# Connectors.net
KiCad netlist of a schematic drawn in Altium Designer
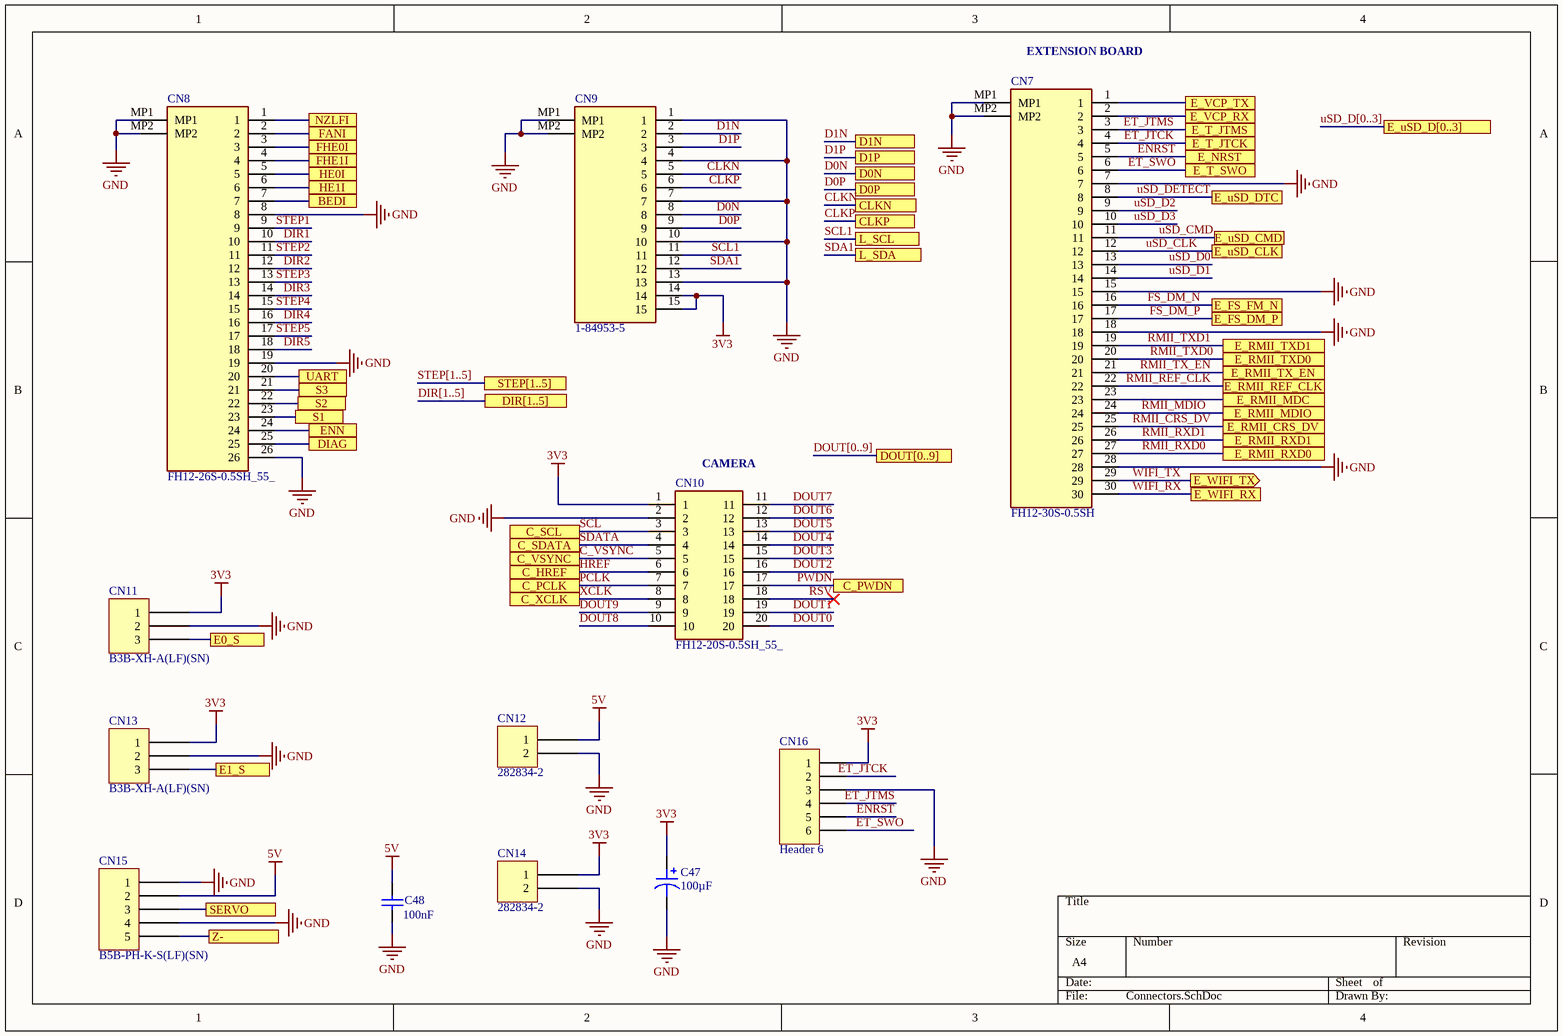
[diagram p0: Connectors.SchDoc]

(export (version "E")
  (design (tool "Eeschema 10.0.6"))
  (components
    (comp (ref "C47")
      (value "100µF")
      (footprint "CAP ALSMD POLY 5.3MM H6.0MM")
      (description "CAP ALUM POLY 100UF 20% 6.3V SMD")
      (fields
        (field (name "PART NUMBER") "6SVPC100M")
        (field (name "MANUFACTURER") "Panasonic Electronic Components")
      )
      (libsource (lib "Celestial Altium Library - altium_library") (part "Polarised Capacitor"))
    )
    (comp (ref "C48")
      (value "100nF")
      (footprint "1608[0603]")
      (description "Capacitor")
      (fields (field (name "Comment") "X5R") (field (name "PUBLISHER") "Altium Limited"))
      (libsource (lib "Miscellaneous Devices") (part "Cap"))
    )
    (comp (ref "CN7")
      (value "FH12-30S-0.5SH")
      (footprint "SamacSys:FH1230S05SH")
      (description "Connector")
      (libsource (lib "*") (part "FH12-30S-0.5SH"))
    )
    (comp (ref "CN8")
      (value "FH12-26S-0.5SH_55_")
      (footprint "SamacSys:FH1226S05SH55")
      (description "Connector")
      (fields
        (field (name "MANUFACTURER_PART_NUMBER") "FH12-26S-0.5SH(55)")
        (field (name "MOUSER PART NUMBER") "798-FH12-26S-0.5SH55")
      )
      (libsource (lib "SamacSys") (part "FH12-26S-0.5SH_55_"))
    )
    (comp (ref "CN9")
      (value "1-84953-5")
      (footprint "SamacSys:1849535")
      (description "Connector")
      (fields (field (name "MOUSER PART NUMBER") "571-1-84953-5"))
      (libsource (lib "*") (part "1-84953-5"))
    )
    (comp (ref "CN10")
      (value "FH12-20S-0.5SH_55_")
      (footprint "SamacSys:FH12-20S-0.5SH(55)")
      (description "Connector")
      (fields
        (field (name "MANUFACTURER_PART_NUMBER") "FH12-20S-0.5SH(55)")
        (field (name "MOUSER PART NUMBER") "798-FH12-20S-0.5SH55")
      )
      (libsource (lib "*") (part "FH12-20S-0.5SH_55_"))
    )
    (comp (ref "CN11")
      (value "B3B-XH-A(LF)(SN)")
      (footprint "JST XH B3B-XH-A")
      (description "CONN HEADER VERT 3POS 2.5MM")
      (fields (field (name "MANUFACTURER") "JST Sales America Inc."))
      (libsource (lib "Celestial Altium Library - altium_library") (part "3 Pin"))
    )
    (comp (ref "CN12")
      (value "282834-2")
      (footprint "TE 282834-2")
      (description "TERM BLK 2P SIDE ENT 2.54MM PCB")
      (fields (field (name "MANUFACTURER") "TE Connectivity AMP Connectors") (field (name "VOLTAGE") "150V"))
      (libsource (lib "Celestial Altium Library - altium_library") (part "2 Pin"))
    )
    (comp (ref "CN13")
      (value "B3B-XH-A(LF)(SN)")
      (footprint "JST XH B3B-XH-A")
      (description "CONN HEADER VERT 3POS 2.5MM")
      (fields (field (name "MANUFACTURER") "JST Sales America Inc."))
      (libsource (lib "Celestial Altium Library - altium_library") (part "3 Pin"))
    )
    (comp (ref "CN14")
      (value "282834-2")
      (footprint "TE 282834-2")
      (description "TERM BLK 2P SIDE ENT 2.54MM PCB")
      (fields (field (name "MANUFACTURER") "TE Connectivity AMP Connectors") (field (name "VOLTAGE") "150V"))
      (libsource (lib "Celestial Altium Library - altium_library") (part "2 Pin"))
    )
    (comp (ref "CN15")
      (value "B5B-PH-K-S(LF)(SN)")
      (footprint "JST B5B-PH-K")
      (description "CONN HEADER VERT 5POS 2MM")
      (fields (field (name "MANUFACTURER") "JST Sales America Inc."))
      (libsource (lib "Celestial Altium Library - altium_library") (part "5 Pin"))
    )
    (comp (ref "CN16")
      (value "Header 6")
      (footprint "HDR1X6")
      (description "Header, 6-Pin")
      (fields (field (name "PUBLISHER") "Altium Limited"))
      (libsource (lib "Miscellaneous Connectors") (part "Header 6"))
    )
  )
  (nets
    (net (code "1") (name "/BEDI") (class "Default")
      (node (ref "CN8") (pin "7") (pinfunction "7_7") (pintype "passive"))
    )
    (net (code "2") (name "/CLKN") (class "Default")
      (node (ref "CN9") (pin "5") (pinfunction "5_5") (pintype "passive"))
    )
    (net (code "3") (name "/CLKP") (class "Default")
      (node (ref "CN9") (pin "6") (pinfunction "6_6") (pintype "passive"))
    )
    (net (code "4") (name "/C_VSYNC") (class "Default")
      (node (ref "CN10") (pin "5") (pinfunction "5_5") (pintype "passive"))
    )
    (net (code "5") (name "/D0N") (class "Default")
      (node (ref "CN9") (pin "8") (pinfunction "8_8") (pintype "passive"))
    )
    (net (code "6") (name "/D0P") (class "Default")
      (node (ref "CN9") (pin "9") (pinfunction "9_9") (pintype "passive"))
    )
    (net (code "7") (name "/D1N") (class "Default")
      (node (ref "CN9") (pin "2") (pinfunction "2_2") (pintype "passive"))
    )
    (net (code "8") (name "/D1P") (class "Default")
      (node (ref "CN9") (pin "3") (pinfunction "3_3") (pintype "passive"))
    )
    (net (code "9") (name "/DIAG") (class "Default")
      (node (ref "CN8") (pin "25") (pinfunction "25_25") (pintype "passive"))
    )
    (net (code "10") (name "/DIR1") (class "Default")
      (node (ref "CN8") (pin "10") (pinfunction "10_10") (pintype "passive"))
    )
    (net (code "11") (name "/DIR2") (class "Default")
      (node (ref "CN8") (pin "12") (pinfunction "12_12") (pintype "passive"))
    )
    (net (code "12") (name "/DIR3") (class "Default")
      (node (ref "CN8") (pin "14") (pinfunction "14_14") (pintype "passive"))
    )
    (net (code "13") (name "/DIR4") (class "Default")
      (node (ref "CN8") (pin "16") (pinfunction "16_16") (pintype "passive"))
    )
    (net (code "14") (name "/DIR5") (class "Default")
      (node (ref "CN8") (pin "18") (pinfunction "18_18") (pintype "passive"))
    )
    (net (code "16") (name "/DOUT0") (class "Default")
      (node (ref "CN10") (pin "20") (pinfunction "20_20") (pintype "passive"))
    )
    (net (code "17") (name "/DOUT1") (class "Default")
      (node (ref "CN10") (pin "19") (pinfunction "19_19") (pintype "passive"))
    )
    (net (code "18") (name "/DOUT2") (class "Default")
      (node (ref "CN10") (pin "16") (pinfunction "16_16") (pintype "passive"))
    )
    (net (code "19") (name "/DOUT3") (class "Default")
      (node (ref "CN10") (pin "15") (pinfunction "15_15") (pintype "passive"))
    )
    (net (code "20") (name "/DOUT4") (class "Default")
      (node (ref "CN10") (pin "14") (pinfunction "14_14") (pintype "passive"))
    )
    (net (code "21") (name "/DOUT5") (class "Default")
      (node (ref "CN10") (pin "13") (pinfunction "13_13") (pintype "passive"))
    )
    (net (code "22") (name "/DOUT6") (class "Default")
      (node (ref "CN10") (pin "12") (pinfunction "12_12") (pintype "passive"))
    )
    (net (code "23") (name "/DOUT7") (class "Default")
      (node (ref "CN10") (pin "11") (pinfunction "11_11") (pintype "passive"))
    )
    (net (code "24") (name "/DOUT8") (class "Default")
      (node (ref "CN10") (pin "10") (pinfunction "10_10") (pintype "passive"))
    )
    (net (code "25") (name "/DOUT9") (class "Default")
      (node (ref "CN10") (pin "9") (pinfunction "9_9") (pintype "passive"))
    )
    (net (code "27") (name "/E0_S") (class "Default")
      (node (ref "CN11") (pin "3") (pinfunction "3_3") (pintype "passive"))
    )
    (net (code "28") (name "/E1_S") (class "Default")
      (node (ref "CN13") (pin "3") (pinfunction "3_3") (pintype "passive"))
    )
    (net (code "29") (name "/ENN") (class "Default")
      (node (ref "CN8") (pin "24") (pinfunction "24_24") (pintype "passive"))
    )
    (net (code "30") (name "/ENRST") (class "Default")
      (node (ref "CN16") (pin "5") (pinfunction "5_5") (pintype "passive"))
      (node (ref "CN7") (pin "5") (pinfunction "5_5") (pintype "passive"))
    )
    (net (code "31") (name "/ET_JTCK") (class "Default")
      (node (ref "CN16") (pin "2") (pinfunction "2_2") (pintype "passive"))
      (node (ref "CN7") (pin "4") (pinfunction "4_4") (pintype "passive"))
    )
    (net (code "32") (name "/ET_JTMS") (class "Default")
      (node (ref "CN16") (pin "4") (pinfunction "4_4") (pintype "passive"))
      (node (ref "CN7") (pin "3") (pinfunction "3_3") (pintype "passive"))
    )
    (net (code "33") (name "/ET_SWO") (class "Default")
      (node (ref "CN16") (pin "6") (pinfunction "6_6") (pintype "passive"))
      (node (ref "CN7") (pin "6") (pinfunction "6_6") (pintype "passive"))
    )
    (net (code "34") (name "/E_RMII_MDC") (class "Default")
      (node (ref "CN7") (pin "23") (pinfunction "23_23") (pintype "passive"))
    )
    (net (code "35") (name "/E_VCP_RX") (class "Default")
      (node (ref "CN7") (pin "2") (pinfunction "2_2") (pintype "passive"))
    )
    (net (code "36") (name "/E_VCP_TX") (class "Default")
      (node (ref "CN7") (pin "1") (pinfunction "1_1") (pintype "passive"))
    )
    (net (code "37") (name "/FANI") (class "Default")
      (node (ref "CN8") (pin "2") (pinfunction "2_2") (pintype "passive"))
    )
    (net (code "38") (name "/FHE0I") (class "Default")
      (node (ref "CN8") (pin "3") (pinfunction "3_3") (pintype "passive"))
    )
    (net (code "39") (name "/FHE1I") (class "Default")
      (node (ref "CN8") (pin "4") (pinfunction "4_4") (pintype "passive"))
    )
    (net (code "40") (name "/FS_DM_N") (class "Default")
      (node (ref "CN7") (pin "16") (pinfunction "16_16") (pintype "passive"))
    )
    (net (code "41") (name "/FS_DM_P") (class "Default")
      (node (ref "CN7") (pin "17") (pinfunction "17_17") (pintype "passive"))
    )
    (net (code "42") (name "/HE0I") (class "Default")
      (node (ref "CN8") (pin "5") (pinfunction "5_5") (pintype "passive"))
    )
    (net (code "43") (name "/HE1I") (class "Default")
      (node (ref "CN8") (pin "6") (pinfunction "6_6") (pintype "passive"))
    )
    (net (code "44") (name "/HREF") (class "Default")
      (node (ref "CN10") (pin "6") (pinfunction "6_6") (pintype "passive"))
    )
    (net (code "45") (name "/NZLFI") (class "Default")
      (node (ref "CN8") (pin "1") (pinfunction "1_1") (pintype "passive"))
    )
    (net (code "46") (name "/PCLK") (class "Default")
      (node (ref "CN10") (pin "7") (pinfunction "7_7") (pintype "passive"))
    )
    (net (code "47") (name "/PWDN") (class "Default")
      (node (ref "CN10") (pin "17") (pinfunction "17_17") (pintype "passive"))
    )
    (net (code "48") (name "/RMII_CRS_DV") (class "Default")
      (node (ref "CN7") (pin "25") (pinfunction "25_25") (pintype "passive"))
    )
    (net (code "49") (name "/RMII_MDIO") (class "Default")
      (node (ref "CN7") (pin "24") (pinfunction "24_24") (pintype "passive"))
    )
    (net (code "50") (name "/RMII_REF_CLK") (class "Default")
      (node (ref "CN7") (pin "22") (pinfunction "22_22") (pintype "passive"))
    )
    (net (code "51") (name "/RMII_RXD0") (class "Default")
      (node (ref "CN7") (pin "27") (pinfunction "27_27") (pintype "passive"))
    )
    (net (code "52") (name "/RMII_RXD1") (class "Default")
      (node (ref "CN7") (pin "26") (pinfunction "26_26") (pintype "passive"))
    )
    (net (code "53") (name "/RMII_TXD0") (class "Default")
      (node (ref "CN7") (pin "20") (pinfunction "20_20") (pintype "passive"))
    )
    (net (code "54") (name "/RMII_TXD1") (class "Default")
      (node (ref "CN7") (pin "19") (pinfunction "19_19") (pintype "passive"))
    )
    (net (code "55") (name "/RMII_TX_EN") (class "Default")
      (node (ref "CN7") (pin "21") (pinfunction "21_21") (pintype "passive"))
    )
    (net (code "56") (name "/RSV") (class "Default")
      (node (ref "CN10") (pin "18") (pinfunction "18_18") (pintype "passive+no_connect"))
    )
    (net (code "57") (name "/S1") (class "Default")
      (node (ref "CN8") (pin "23") (pinfunction "23_23") (pintype "passive"))
    )
    (net (code "58") (name "/S2") (class "Default")
      (node (ref "CN8") (pin "22") (pinfunction "22_22") (pintype "passive"))
    )
    (net (code "59") (name "/S3") (class "Default")
      (node (ref "CN8") (pin "21") (pinfunction "21_21") (pintype "passive"))
    )
    (net (code "60") (name "/SCL") (class "Default")
      (node (ref "CN10") (pin "3") (pinfunction "3_3") (pintype "passive"))
    )
    (net (code "61") (name "/SCL1") (class "Default")
      (node (ref "CN9") (pin "11") (pinfunction "11_11") (pintype "passive"))
    )
    (net (code "62") (name "/SDA1") (class "Default")
      (node (ref "CN9") (pin "12") (pinfunction "12_12") (pintype "passive"))
    )
    (net (code "63") (name "/SDATA") (class "Default")
      (node (ref "CN10") (pin "4") (pinfunction "4_4") (pintype "passive"))
    )
    (net (code "64") (name "/SERVO") (class "Default")
      (node (ref "CN15") (pin "3") (pinfunction "3_3") (pintype "passive"))
    )
    (net (code "65") (name "/STEP1") (class "Default")
      (node (ref "CN8") (pin "9") (pinfunction "9_9") (pintype "passive"))
    )
    (net (code "66") (name "/STEP2") (class "Default")
      (node (ref "CN8") (pin "11") (pinfunction "11_11") (pintype "passive"))
    )
    (net (code "67") (name "/STEP3") (class "Default")
      (node (ref "CN8") (pin "13") (pinfunction "13_13") (pintype "passive"))
    )
    (net (code "68") (name "/STEP4") (class "Default")
      (node (ref "CN8") (pin "15") (pinfunction "15_15") (pintype "passive"))
    )
    (net (code "69") (name "/STEP5") (class "Default")
      (node (ref "CN8") (pin "17") (pinfunction "17_17") (pintype "passive"))
    )
    (net (code "71") (name "/UART") (class "Default")
      (node (ref "CN8") (pin "20") (pinfunction "20_20") (pintype "passive"))
    )
    (net (code "72") (name "/WIFI_RX") (class "Default")
      (node (ref "CN7") (pin "30") (pinfunction "30_30") (pintype "passive"))
    )
    (net (code "73") (name "/WIFI_TX") (class "Default")
      (node (ref "CN7") (pin "29") (pinfunction "29_29") (pintype "passive"))
    )
    (net (code "74") (name "/XCLK") (class "Default")
      (node (ref "CN10") (pin "8") (pinfunction "8_8") (pintype "passive"))
    )
    (net (code "75") (name "/Z-") (class "Default")
      (node (ref "CN15") (pin "5") (pinfunction "5_5") (pintype "passive"))
    )
    (net (code "76") (name "/uSD_CLK") (class "Default")
      (node (ref "CN7") (pin "12") (pinfunction "12_12") (pintype "passive"))
    )
    (net (code "77") (name "/uSD_CMD") (class "Default")
      (node (ref "CN7") (pin "11") (pinfunction "11_11") (pintype "passive"))
    )
    (net (code "78") (name "/uSD_D0") (class "Default")
      (node (ref "CN7") (pin "13") (pinfunction "13_13") (pintype "passive"))
    )
    (net (code "79") (name "/uSD_D1") (class "Default")
      (node (ref "CN7") (pin "14") (pinfunction "14_14") (pintype "passive"))
    )
    (net (code "80") (name "/uSD_D2") (class "Default")
      (node (ref "CN7") (pin "9") (pinfunction "9_9") (pintype "passive"))
    )
    (net (code "81") (name "/uSD_D3") (class "Default")
      (node (ref "CN7") (pin "10") (pinfunction "10_10") (pintype "passive"))
    )
    (net (code "82") (name "/uSD_DETECT") (class "Default")
      (node (ref "CN7") (pin "8") (pinfunction "8_8") (pintype "passive"))
    )
    (net (code "84") (name "3V3") (class "Default")
      (node (ref "C47") (pin "1") (pinfunction "1_1") (pintype "passive"))
      (node (ref "CN10") (pin "1") (pinfunction "1_1") (pintype "passive"))
      (node (ref "CN11") (pin "1") (pinfunction "1_1") (pintype "passive"))
      (node (ref "CN13") (pin "1") (pinfunction "1_1") (pintype "passive"))
      (node (ref "CN14") (pin "1") (pinfunction "1_1") (pintype "passive"))
      (node (ref "CN16") (pin "1") (pinfunction "1_1") (pintype "passive"))
      (node (ref "CN9") (pin "14") (pinfunction "14_14") (pintype "passive"))
      (node (ref "CN9") (pin "15") (pinfunction "15_15") (pintype "passive"))
    )
    (net (code "85") (name "5V") (class "Default")
      (node (ref "C48") (pin "1") (pinfunction "1_1") (pintype "passive"))
      (node (ref "CN12") (pin "1") (pinfunction "1_1") (pintype "passive"))
      (node (ref "CN15") (pin "2") (pinfunction "2_2") (pintype "passive"))
    )
    (net (code "86") (name "GND") (class "Default")
      (node (ref "C47") (pin "2") (pinfunction "2_2") (pintype "passive"))
      (node (ref "C48") (pin "2") (pinfunction "2_2") (pintype "passive"))
      (node (ref "CN10") (pin "2") (pinfunction "2_2") (pintype "passive"))
      (node (ref "CN11") (pin "2") (pinfunction "2_2") (pintype "passive"))
      (node (ref "CN12") (pin "2") (pinfunction "2_2") (pintype "passive"))
      (node (ref "CN13") (pin "2") (pinfunction "2_2") (pintype "passive"))
      (node (ref "CN14") (pin "2") (pinfunction "2_2") (pintype "passive"))
      (node (ref "CN15") (pin "1") (pinfunction "1_1") (pintype "passive"))
      (node (ref "CN15") (pin "4") (pinfunction "4_4") (pintype "passive"))
      (node (ref "CN16") (pin "3") (pinfunction "3_3") (pintype "passive"))
      (node (ref "CN7") (pin "15") (pinfunction "15_15") (pintype "passive"))
      (node (ref "CN7") (pin "18") (pinfunction "18_18") (pintype "passive"))
      (node (ref "CN7") (pin "28") (pinfunction "28_28") (pintype "passive"))
      (node (ref "CN7") (pin "7") (pinfunction "7_7") (pintype "passive"))
      (node (ref "CN7") (pin "MP1") (pinfunction "MP1_MP1") (pintype "passive"))
      (node (ref "CN7") (pin "MP2") (pinfunction "MP2_MP2") (pintype "passive"))
      (node (ref "CN8") (pin "19") (pinfunction "19_19") (pintype "passive"))
      (node (ref "CN8") (pin "26") (pinfunction "26_26") (pintype "passive"))
      (node (ref "CN8") (pin "8") (pinfunction "8_8") (pintype "passive"))
      (node (ref "CN8") (pin "MP1") (pinfunction "MP1_MP1") (pintype "passive"))
      (node (ref "CN8") (pin "MP2") (pinfunction "MP2_MP2") (pintype "passive"))
      (node (ref "CN9") (pin "1") (pinfunction "1_1") (pintype "passive"))
      (node (ref "CN9") (pin "10") (pinfunction "10_10") (pintype "passive"))
      (node (ref "CN9") (pin "13") (pinfunction "13_13") (pintype "passive"))
      (node (ref "CN9") (pin "4") (pinfunction "4_4") (pintype "passive"))
      (node (ref "CN9") (pin "7") (pinfunction "7_7") (pintype "passive"))
      (node (ref "CN9") (pin "MP1") (pinfunction "MP1_MP1") (pintype "passive"))
      (node (ref "CN9") (pin "MP2") (pinfunction "MP2_MP2") (pintype "passive"))
    )
  )
)
